# CTR-Controller-Rev-A-LED-5.net
KiCad netlist of a schematic drawn in Altium Designer
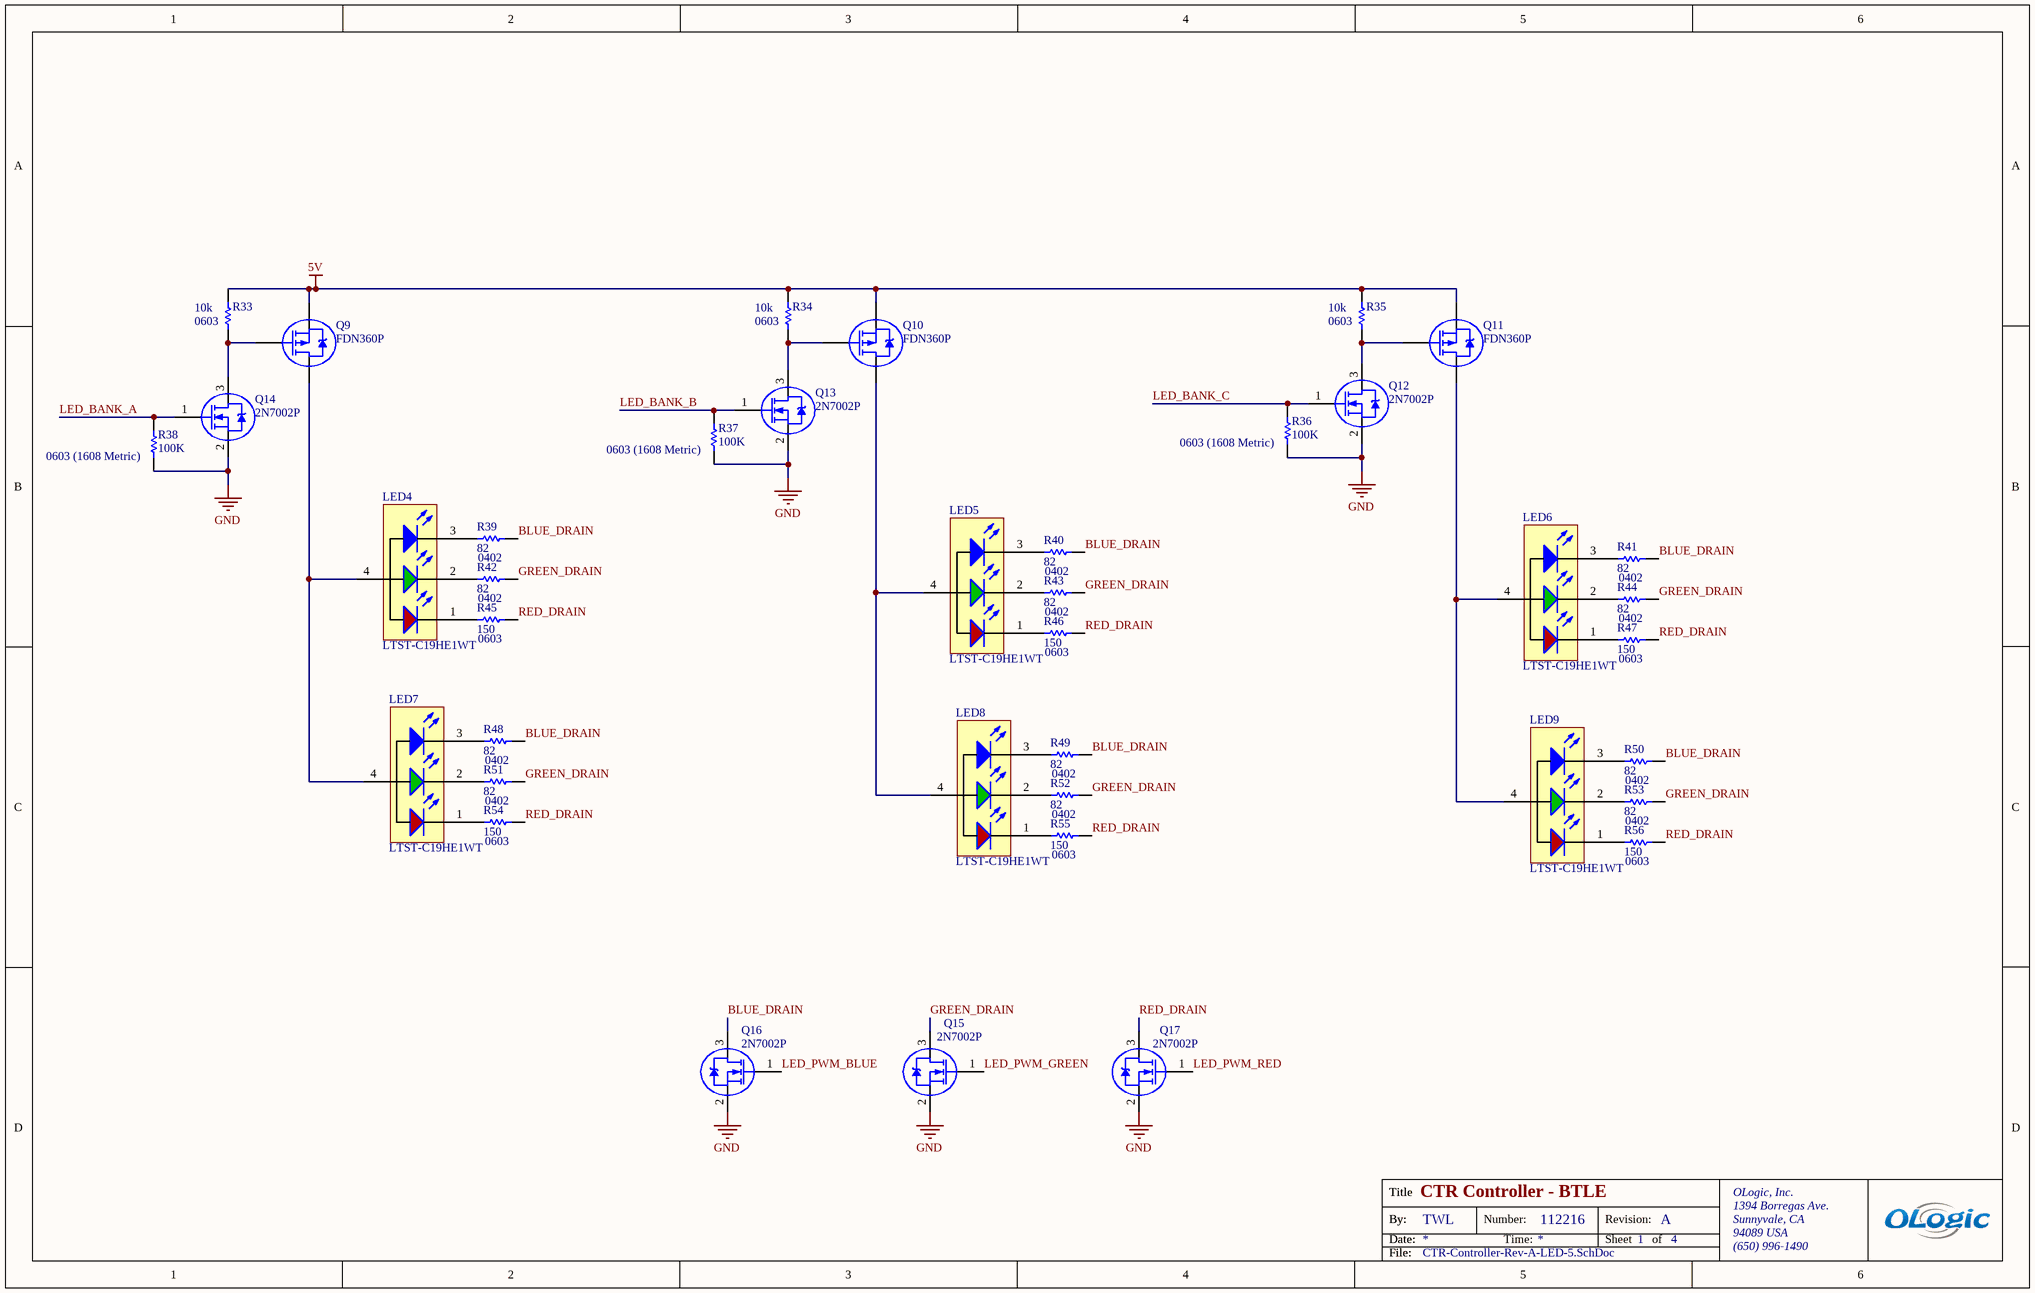
[diagram p0: CTR-Controller-Rev-A-LED-5.SchDoc]

(export (version "E")
  (design (tool "Eeschema 10.0.6"))
  (components
    (comp (ref "LED4")
      (value "Red, Green, Blue (RGB)")
      (footprint "LTST-C19HE1WT")
      (description "LED RGB 624/525/470NM DIFF SMD")
      (fields
        (field (name "MANUFACTURER") "Lite-On Inc.")
        (field (name "MANUFACTURER PART NUMBER") "LTST-C19HE1WT")
      )
      (libsource (lib "OLogic-Diode-Opto-LED") (part "LTST-C19HE1WT"))
    )
    (comp (ref "LED5")
      (value "Red, Green, Blue (RGB)")
      (footprint "LTST-C19HE1WT")
      (description "LED RGB 624/525/470NM DIFF SMD")
      (fields
        (field (name "MANUFACTURER") "Lite-On Inc.")
        (field (name "MANUFACTURER PART NUMBER") "LTST-C19HE1WT")
      )
      (libsource (lib "OLogic-Diode-Opto-LED") (part "LTST-C19HE1WT"))
    )
    (comp (ref "LED6")
      (value "Red, Green, Blue (RGB)")
      (footprint "LTST-C19HE1WT")
      (description "LED RGB 624/525/470NM DIFF SMD")
      (fields
        (field (name "MANUFACTURER") "Lite-On Inc.")
        (field (name "MANUFACTURER PART NUMBER") "LTST-C19HE1WT")
      )
      (libsource (lib "OLogic-Diode-Opto-LED") (part "LTST-C19HE1WT"))
    )
    (comp (ref "LED7")
      (value "Red, Green, Blue (RGB)")
      (footprint "LTST-C19HE1WT")
      (description "LED RGB 624/525/470NM DIFF SMD")
      (fields
        (field (name "MANUFACTURER") "Lite-On Inc.")
        (field (name "MANUFACTURER PART NUMBER") "LTST-C19HE1WT")
      )
      (libsource (lib "OLogic-Diode-Opto-LED") (part "LTST-C19HE1WT"))
    )
    (comp (ref "LED8")
      (value "Red, Green, Blue (RGB)")
      (footprint "LTST-C19HE1WT")
      (description "LED RGB 624/525/470NM DIFF SMD")
      (fields
        (field (name "MANUFACTURER") "Lite-On Inc.")
        (field (name "MANUFACTURER PART NUMBER") "LTST-C19HE1WT")
      )
      (libsource (lib "OLogic-Diode-Opto-LED") (part "LTST-C19HE1WT"))
    )
    (comp (ref "LED9")
      (value "Red, Green, Blue (RGB)")
      (footprint "LTST-C19HE1WT")
      (description "LED RGB 624/525/470NM DIFF SMD")
      (fields
        (field (name "MANUFACTURER") "Lite-On Inc.")
        (field (name "MANUFACTURER PART NUMBER") "LTST-C19HE1WT")
      )
      (libsource (lib "OLogic-Diode-Opto-LED") (part "LTST-C19HE1WT"))
    )
    (comp (ref "Q9")
      (value "FDN360P")
      (footprint "SOT23")
      (description "Single P-Channel MOSFET")
      (fields (field (name "MANUFACTURER") "Fairchild Semi"))
      (libsource (lib "OLogic-Trans-Drivers") (part "FDN360P"))
    )
    (comp (ref "Q10")
      (value "FDN360P")
      (footprint "SOT23")
      (description "Single P-Channel MOSFET")
      (fields (field (name "MANUFACTURER") "Fairchild Semi"))
      (libsource (lib "OLogic-Trans-Drivers") (part "FDN360P"))
    )
    (comp (ref "Q11")
      (value "FDN360P")
      (footprint "SOT23")
      (description "Single P-Channel MOSFET")
      (fields (field (name "MANUFACTURER") "Fairchild Semi"))
      (libsource (lib "OLogic-Trans-Drivers") (part "FDN360P"))
    )
    (comp (ref "Q12")
      (value "2N7002P")
      (footprint "SOT23")
      (description "MOSFET N-CH 60V 0.36A SOT-23")
      (fields
        (field (name "MANUFACTURER") "NXP Semiconductors")
        (field (name "MANUFACTURER PART NUMBER") "2N7002P,235")
      )
      (libsource (lib "") (part "2N7002P_1"))
    )
    (comp (ref "Q13")
      (value "2N7002P")
      (footprint "SOT23")
      (description "MOSFET N-CH 60V 0.36A SOT-23")
      (fields
        (field (name "MANUFACTURER") "NXP Semiconductors")
        (field (name "MANUFACTURER PART NUMBER") "2N7002P,235")
      )
      (libsource (lib "") (part "2N7002P_1"))
    )
    (comp (ref "Q14")
      (value "2N7002P")
      (footprint "SOT23")
      (description "MOSFET N-CH 60V 0.36A SOT-23")
      (fields
        (field (name "MANUFACTURER") "NXP Semiconductors")
        (field (name "MANUFACTURER PART NUMBER") "2N7002P,235")
      )
      (libsource (lib "") (part "2N7002P_1"))
    )
    (comp (ref "Q15")
      (value "2N7002P")
      (footprint "SOT23")
      (description "MOSFET N-CH 60V 0.36A SOT-23")
      (fields
        (field (name "MANUFACTURER") "NXP Semiconductors")
        (field (name "MANUFACTURER PART NUMBER") "2N7002P,235")
      )
      (libsource (lib "OLogic-Trans-Drivers") (part "2N7002P"))
    )
    (comp (ref "Q16")
      (value "2N7002P")
      (footprint "SOT23")
      (description "MOSFET N-CH 60V 0.36A SOT-23")
      (fields
        (field (name "MANUFACTURER") "NXP Semiconductors")
        (field (name "MANUFACTURER PART NUMBER") "2N7002P,235")
      )
      (libsource (lib "OLogic-Trans-Drivers") (part "2N7002P"))
    )
    (comp (ref "Q17")
      (value "2N7002P")
      (footprint "SOT23")
      (description "MOSFET N-CH 60V 0.36A SOT-23")
      (fields
        (field (name "MANUFACTURER") "NXP Semiconductors")
        (field (name "MANUFACTURER PART NUMBER") "2N7002P,235")
      )
      (libsource (lib "OLogic-Trans-Drivers") (part "2N7002P"))
    )
    (comp (ref "R33")
      (value "10K 1%")
      (footprint "RESC0603(1608)_N")
      (description "10K 0603")
      (fields
        (field (name "MANUFACTURER") "Panasonic Electronic Components")
        (field (name "MANUFACTURER PART NUMBER") "ERJ-3EKF1002V")
        (field (name "RESISTANCE (OHMS)") "10k")
        (field (name "SUPPLIER DEVICE PACKAGE") "0603")
      )
      (libsource (lib "OLogic-Passive") (part "RES 10K OHM 1/10W 1% 0603 SMD"))
    )
    (comp (ref "R34")
      (value "10K 1%")
      (footprint "RESC0603(1608)_N")
      (description "10K 0603")
      (fields
        (field (name "MANUFACTURER") "Panasonic Electronic Components")
        (field (name "MANUFACTURER PART NUMBER") "ERJ-3EKF1002V")
        (field (name "RESISTANCE (OHMS)") "10k")
        (field (name "SUPPLIER DEVICE PACKAGE") "0603")
      )
      (libsource (lib "OLogic-Passive") (part "RES 10K OHM 1/10W 1% 0603 SMD"))
    )
    (comp (ref "R35")
      (value "10K 1%")
      (footprint "RESC0603(1608)_N")
      (description "10K 0603")
      (fields
        (field (name "MANUFACTURER") "Panasonic Electronic Components")
        (field (name "MANUFACTURER PART NUMBER") "ERJ-3EKF1002V")
        (field (name "RESISTANCE (OHMS)") "10k")
        (field (name "SUPPLIER DEVICE PACKAGE") "0603")
      )
      (libsource (lib "OLogic-Passive") (part "RES 10K OHM 1/10W 1% 0603 SMD"))
    )
    (comp (ref "R36")
      (value "100K")
      (footprint "RESC0603(1608)_N")
      (description "100K 0603")
      (fields
        (field (name "MANUFACTURER") "Rohm Semiconductor")
        (field (name "MANUFACTURER PART NUMBER") "ESR03EZPJ104")
        (field (name "PACKAGE / CASE") "0603 (1608 Metric)")
      )
      (libsource (lib "OLogic-Passive") (part "RES 100K OHM 5% 1/4W 0603"))
    )
    (comp (ref "R37")
      (value "100K")
      (footprint "RESC0603(1608)_N")
      (description "100K 0603")
      (fields
        (field (name "MANUFACTURER") "Rohm Semiconductor")
        (field (name "MANUFACTURER PART NUMBER") "ESR03EZPJ104")
        (field (name "PACKAGE / CASE") "0603 (1608 Metric)")
      )
      (libsource (lib "OLogic-Passive") (part "RES 100K OHM 5% 1/4W 0603"))
    )
    (comp (ref "R38")
      (value "100K")
      (footprint "RESC0603(1608)_N")
      (description "100K 0603")
      (fields
        (field (name "MANUFACTURER") "Rohm Semiconductor")
        (field (name "MANUFACTURER PART NUMBER") "ESR03EZPJ104")
        (field (name "PACKAGE / CASE") "0603 (1608 Metric)")
      )
      (libsource (lib "OLogic-Passive") (part "RES 100K OHM 5% 1/4W 0603"))
    )
    (comp (ref "R39")
      (value "?")
      (footprint "RESC0402(1005)_N")
      (description "82 0402")
      (fields
        (field (name "MANUFACTURER") "Panasonic Electronic Components")
        (field (name "MANUFACTURER PART NUMBER") "ERJ-2RKF82R0X")
        (field (name "SUPPLIER DEVICE PACKAGE") "0402")
        (field (name "RESISTANCE (OHMS)") "82")
        (field (name "CREATOR") "osman")
      )
      (libsource (lib "OLogic-Passive") (part "RES 82 OHM 1% 1/10W 0402"))
    )
    (comp (ref "R40")
      (value "?")
      (footprint "RESC0402(1005)_N")
      (description "82 0402")
      (fields
        (field (name "MANUFACTURER") "Panasonic Electronic Components")
        (field (name "MANUFACTURER PART NUMBER") "ERJ-2RKF82R0X")
        (field (name "SUPPLIER DEVICE PACKAGE") "0402")
        (field (name "RESISTANCE (OHMS)") "82")
        (field (name "CREATOR") "osman")
      )
      (libsource (lib "OLogic-Passive") (part "RES 82 OHM 1% 1/10W 0402"))
    )
    (comp (ref "R41")
      (value "?")
      (footprint "RESC0402(1005)_N")
      (description "82 0402")
      (fields
        (field (name "MANUFACTURER") "Panasonic Electronic Components")
        (field (name "MANUFACTURER PART NUMBER") "ERJ-2RKF82R0X")
        (field (name "SUPPLIER DEVICE PACKAGE") "0402")
        (field (name "RESISTANCE (OHMS)") "82")
        (field (name "CREATOR") "osman")
      )
      (libsource (lib "OLogic-Passive") (part "RES 82 OHM 1% 1/10W 0402"))
    )
    (comp (ref "R42")
      (value "?")
      (footprint "RESC0402(1005)_N")
      (description "82 0402")
      (fields
        (field (name "MANUFACTURER") "Panasonic Electronic Components")
        (field (name "MANUFACTURER PART NUMBER") "ERJ-2RKF82R0X")
        (field (name "SUPPLIER DEVICE PACKAGE") "0402")
        (field (name "RESISTANCE (OHMS)") "82")
        (field (name "CREATOR") "osman")
      )
      (libsource (lib "OLogic-Passive") (part "RES 82 OHM 1% 1/10W 0402"))
    )
    (comp (ref "R43")
      (value "?")
      (footprint "RESC0402(1005)_N")
      (description "82 0402")
      (fields
        (field (name "MANUFACTURER") "Panasonic Electronic Components")
        (field (name "MANUFACTURER PART NUMBER") "ERJ-2RKF82R0X")
        (field (name "SUPPLIER DEVICE PACKAGE") "0402")
        (field (name "RESISTANCE (OHMS)") "82")
        (field (name "CREATOR") "osman")
      )
      (libsource (lib "OLogic-Passive") (part "RES 82 OHM 1% 1/10W 0402"))
    )
    (comp (ref "R44")
      (value "?")
      (footprint "RESC0402(1005)_N")
      (description "82 0402")
      (fields
        (field (name "MANUFACTURER") "Panasonic Electronic Components")
        (field (name "MANUFACTURER PART NUMBER") "ERJ-2RKF82R0X")
        (field (name "SUPPLIER DEVICE PACKAGE") "0402")
        (field (name "RESISTANCE (OHMS)") "82")
        (field (name "CREATOR") "osman")
      )
      (libsource (lib "OLogic-Passive") (part "RES 82 OHM 1% 1/10W 0402"))
    )
    (comp (ref "R45")
      (value "150")
      (footprint "RESC0603(1608)_N")
      (description "150 0603")
      (fields
        (field (name "MANUFACTURER") "Yageo")
        (field (name "MANUFACTURER PART NUMBER") "RC0603FR-07150RL")
        (field (name "SUPPLIER DEVICE PACKAGE") "0603")
      )
      (libsource (lib "OLogic-Passive") (part "RES 150 OHM 1/10W 1% 0603 SMD"))
    )
    (comp (ref "R46")
      (value "150")
      (footprint "RESC0603(1608)_N")
      (description "150 0603")
      (fields
        (field (name "MANUFACTURER") "Yageo")
        (field (name "MANUFACTURER PART NUMBER") "RC0603FR-07150RL")
        (field (name "SUPPLIER DEVICE PACKAGE") "0603")
      )
      (libsource (lib "OLogic-Passive") (part "RES 150 OHM 1/10W 1% 0603 SMD"))
    )
    (comp (ref "R47")
      (value "150")
      (footprint "RESC0603(1608)_N")
      (description "150 0603")
      (fields
        (field (name "MANUFACTURER") "Yageo")
        (field (name "MANUFACTURER PART NUMBER") "RC0603FR-07150RL")
        (field (name "SUPPLIER DEVICE PACKAGE") "0603")
      )
      (libsource (lib "OLogic-Passive") (part "RES 150 OHM 1/10W 1% 0603 SMD"))
    )
    (comp (ref "R48")
      (value "?")
      (footprint "RESC0402(1005)_N")
      (description "82 0402")
      (fields
        (field (name "MANUFACTURER") "Panasonic Electronic Components")
        (field (name "MANUFACTURER PART NUMBER") "ERJ-2RKF82R0X")
        (field (name "SUPPLIER DEVICE PACKAGE") "0402")
        (field (name "RESISTANCE (OHMS)") "82")
        (field (name "CREATOR") "osman")
      )
      (libsource (lib "OLogic-Passive") (part "RES 82 OHM 1% 1/10W 0402"))
    )
    (comp (ref "R49")
      (value "?")
      (footprint "RESC0402(1005)_N")
      (description "82 0402")
      (fields
        (field (name "MANUFACTURER") "Panasonic Electronic Components")
        (field (name "MANUFACTURER PART NUMBER") "ERJ-2RKF82R0X")
        (field (name "SUPPLIER DEVICE PACKAGE") "0402")
        (field (name "RESISTANCE (OHMS)") "82")
        (field (name "CREATOR") "osman")
      )
      (libsource (lib "OLogic-Passive") (part "RES 82 OHM 1% 1/10W 0402"))
    )
    (comp (ref "R50")
      (value "?")
      (footprint "RESC0402(1005)_N")
      (description "82 0402")
      (fields
        (field (name "MANUFACTURER") "Panasonic Electronic Components")
        (field (name "MANUFACTURER PART NUMBER") "ERJ-2RKF82R0X")
        (field (name "SUPPLIER DEVICE PACKAGE") "0402")
        (field (name "RESISTANCE (OHMS)") "82")
        (field (name "CREATOR") "osman")
      )
      (libsource (lib "OLogic-Passive") (part "RES 82 OHM 1% 1/10W 0402"))
    )
    (comp (ref "R51")
      (value "?")
      (footprint "RESC0402(1005)_N")
      (description "82 0402")
      (fields
        (field (name "MANUFACTURER") "Panasonic Electronic Components")
        (field (name "MANUFACTURER PART NUMBER") "ERJ-2RKF82R0X")
        (field (name "SUPPLIER DEVICE PACKAGE") "0402")
        (field (name "RESISTANCE (OHMS)") "82")
        (field (name "CREATOR") "osman")
      )
      (libsource (lib "OLogic-Passive") (part "RES 82 OHM 1% 1/10W 0402"))
    )
    (comp (ref "R52")
      (value "?")
      (footprint "RESC0402(1005)_N")
      (description "82 0402")
      (fields
        (field (name "MANUFACTURER") "Panasonic Electronic Components")
        (field (name "MANUFACTURER PART NUMBER") "ERJ-2RKF82R0X")
        (field (name "SUPPLIER DEVICE PACKAGE") "0402")
        (field (name "RESISTANCE (OHMS)") "82")
        (field (name "CREATOR") "osman")
      )
      (libsource (lib "OLogic-Passive") (part "RES 82 OHM 1% 1/10W 0402"))
    )
    (comp (ref "R53")
      (value "?")
      (footprint "RESC0402(1005)_N")
      (description "82 0402")
      (fields
        (field (name "MANUFACTURER") "Panasonic Electronic Components")
        (field (name "MANUFACTURER PART NUMBER") "ERJ-2RKF82R0X")
        (field (name "SUPPLIER DEVICE PACKAGE") "0402")
        (field (name "RESISTANCE (OHMS)") "82")
        (field (name "CREATOR") "osman")
      )
      (libsource (lib "OLogic-Passive") (part "RES 82 OHM 1% 1/10W 0402"))
    )
    (comp (ref "R54")
      (value "150")
      (footprint "RESC0603(1608)_N")
      (description "150 0603")
      (fields
        (field (name "MANUFACTURER") "Yageo")
        (field (name "MANUFACTURER PART NUMBER") "RC0603FR-07150RL")
        (field (name "SUPPLIER DEVICE PACKAGE") "0603")
      )
      (libsource (lib "OLogic-Passive") (part "RES 150 OHM 1/10W 1% 0603 SMD"))
    )
    (comp (ref "R55")
      (value "150")
      (footprint "RESC0603(1608)_N")
      (description "150 0603")
      (fields
        (field (name "MANUFACTURER") "Yageo")
        (field (name "MANUFACTURER PART NUMBER") "RC0603FR-07150RL")
        (field (name "SUPPLIER DEVICE PACKAGE") "0603")
      )
      (libsource (lib "OLogic-Passive") (part "RES 150 OHM 1/10W 1% 0603 SMD"))
    )
    (comp (ref "R56")
      (value "150")
      (footprint "RESC0603(1608)_N")
      (description "150 0603")
      (fields
        (field (name "MANUFACTURER") "Yageo")
        (field (name "MANUFACTURER PART NUMBER") "RC0603FR-07150RL")
        (field (name "SUPPLIER DEVICE PACKAGE") "0603")
      )
      (libsource (lib "OLogic-Passive") (part "RES 150 OHM 1/10W 1% 0603 SMD"))
    )
  )
  (nets
    (net (code "1") (name "/BLUE_DRAIN") (class "Default")
      (node (ref "Q16") (pin "3") (pinfunction "D_3") (pintype "power_in"))
      (node (ref "R39") (pin "1") (pinfunction "1_1") (pintype "passive"))
      (node (ref "R40") (pin "1") (pinfunction "1_1") (pintype "passive"))
      (node (ref "R41") (pin "1") (pinfunction "1_1") (pintype "passive"))
      (node (ref "R48") (pin "1") (pinfunction "1_1") (pintype "passive"))
      (node (ref "R49") (pin "1") (pinfunction "1_1") (pintype "passive"))
      (node (ref "R50") (pin "1") (pinfunction "1_1") (pintype "passive"))
    )
    (net (code "2") (name "/GREEN_DRAIN") (class "Default")
      (node (ref "Q15") (pin "3") (pinfunction "D_3") (pintype "power_in"))
      (node (ref "R42") (pin "1") (pinfunction "1_1") (pintype "passive"))
      (node (ref "R43") (pin "1") (pinfunction "1_1") (pintype "passive"))
      (node (ref "R44") (pin "1") (pinfunction "1_1") (pintype "passive"))
      (node (ref "R51") (pin "1") (pinfunction "1_1") (pintype "passive"))
      (node (ref "R52") (pin "1") (pinfunction "1_1") (pintype "passive"))
      (node (ref "R53") (pin "1") (pinfunction "1_1") (pintype "passive"))
    )
    (net (code "3") (name "/LED_BANK_A") (class "Default")
      (node (ref "Q14") (pin "1") (pinfunction "G_1") (pintype "passive"))
      (node (ref "R38") (pin "2") (pinfunction "2_2") (pintype "passive"))
    )
    (net (code "4") (name "/LED_BANK_B") (class "Default")
      (node (ref "Q13") (pin "1") (pinfunction "G_1") (pintype "passive"))
      (node (ref "R37") (pin "2") (pinfunction "2_2") (pintype "passive"))
    )
    (net (code "5") (name "/LED_BANK_C") (class "Default")
      (node (ref "Q12") (pin "1") (pinfunction "G_1") (pintype "passive"))
      (node (ref "R36") (pin "2") (pinfunction "2_2") (pintype "passive"))
    )
    (net (code "6") (name "/LED_PWM_BLUE") (class "Default")
      (node (ref "Q16") (pin "1") (pinfunction "G_1") (pintype "passive"))
    )
    (net (code "7") (name "/LED_PWM_GREEN") (class "Default")
      (node (ref "Q15") (pin "1") (pinfunction "G_1") (pintype "passive"))
    )
    (net (code "8") (name "/LED_PWM_RED") (class "Default")
      (node (ref "Q17") (pin "1") (pinfunction "G_1") (pintype "passive"))
    )
    (net (code "9") (name "/RED_DRAIN") (class "Default")
      (node (ref "Q17") (pin "3") (pinfunction "D_3") (pintype "power_in"))
      (node (ref "R45") (pin "1") (pinfunction "1_1") (pintype "passive"))
      (node (ref "R46") (pin "1") (pinfunction "1_1") (pintype "passive"))
      (node (ref "R47") (pin "1") (pinfunction "1_1") (pintype "passive"))
      (node (ref "R54") (pin "1") (pinfunction "1_1") (pintype "passive"))
      (node (ref "R55") (pin "1") (pinfunction "1_1") (pintype "passive"))
      (node (ref "R56") (pin "1") (pinfunction "1_1") (pintype "passive"))
    )
    (net (code "10") (name "5V") (class "Default")
      (node (ref "Q10") (pin "2") (pinfunction "S_2") (pintype "passive"))
      (node (ref "Q11") (pin "2") (pinfunction "S_2") (pintype "passive"))
      (node (ref "Q9") (pin "2") (pinfunction "S_2") (pintype "passive"))
      (node (ref "R33") (pin "2") (pinfunction "2_2") (pintype "passive"))
      (node (ref "R34") (pin "2") (pinfunction "2_2") (pintype "passive"))
      (node (ref "R35") (pin "2") (pinfunction "2_2") (pintype "passive"))
    )
    (net (code "11") (name "GND") (class "Default")
      (node (ref "Q12") (pin "2") (pinfunction "S_2") (pintype "passive"))
      (node (ref "Q13") (pin "2") (pinfunction "S_2") (pintype "passive"))
      (node (ref "Q14") (pin "2") (pinfunction "S_2") (pintype "passive"))
      (node (ref "Q15") (pin "2") (pinfunction "S_2") (pintype "passive"))
      (node (ref "Q16") (pin "2") (pinfunction "S_2") (pintype "passive"))
      (node (ref "Q17") (pin "2") (pinfunction "S_2") (pintype "passive"))
      (node (ref "R36") (pin "1") (pinfunction "1_1") (pintype "passive"))
      (node (ref "R37") (pin "1") (pinfunction "1_1") (pintype "passive"))
      (node (ref "R38") (pin "1") (pinfunction "1_1") (pintype "passive"))
    )
    (net (code "12") (name "Net-(LED4-Anode)") (class "Default")
      (node (ref "LED4") (pin "4") (pinfunction "Anode_4") (pintype "passive"))
      (node (ref "LED7") (pin "4") (pinfunction "Anode_4") (pintype "passive"))
      (node (ref "Q9") (pin "3") (pinfunction "D_3") (pintype "passive"))
    )
    (net (code "13") (name "Net-(LED4-B)") (class "Default")
      (node (ref "LED4") (pin "3") (pinfunction "B_3") (pintype "passive"))
      (node (ref "R39") (pin "2") (pinfunction "2_2") (pintype "passive"))
    )
    (net (code "14") (name "Net-(LED4-G)") (class "Default")
      (node (ref "LED4") (pin "2") (pinfunction "G_2") (pintype "passive"))
      (node (ref "R42") (pin "2") (pinfunction "2_2") (pintype "passive"))
    )
    (net (code "15") (name "Net-(LED4-R)") (class "Default")
      (node (ref "LED4") (pin "1") (pinfunction "R_1") (pintype "passive"))
      (node (ref "R45") (pin "2") (pinfunction "2_2") (pintype "passive"))
    )
    (net (code "16") (name "Net-(LED5-Anode)") (class "Default")
      (node (ref "LED5") (pin "4") (pinfunction "Anode_4") (pintype "passive"))
      (node (ref "LED8") (pin "4") (pinfunction "Anode_4") (pintype "passive"))
      (node (ref "Q10") (pin "3") (pinfunction "D_3") (pintype "passive"))
    )
    (net (code "17") (name "Net-(LED5-B)") (class "Default")
      (node (ref "LED5") (pin "3") (pinfunction "B_3") (pintype "passive"))
      (node (ref "R40") (pin "2") (pinfunction "2_2") (pintype "passive"))
    )
    (net (code "18") (name "Net-(LED5-G)") (class "Default")
      (node (ref "LED5") (pin "2") (pinfunction "G_2") (pintype "passive"))
      (node (ref "R43") (pin "2") (pinfunction "2_2") (pintype "passive"))
    )
    (net (code "19") (name "Net-(LED5-R)") (class "Default")
      (node (ref "LED5") (pin "1") (pinfunction "R_1") (pintype "passive"))
      (node (ref "R46") (pin "2") (pinfunction "2_2") (pintype "passive"))
    )
    (net (code "20") (name "Net-(LED6-Anode)") (class "Default")
      (node (ref "LED6") (pin "4") (pinfunction "Anode_4") (pintype "passive"))
      (node (ref "LED9") (pin "4") (pinfunction "Anode_4") (pintype "passive"))
      (node (ref "Q11") (pin "3") (pinfunction "D_3") (pintype "passive"))
    )
    (net (code "21") (name "Net-(LED6-B)") (class "Default")
      (node (ref "LED6") (pin "3") (pinfunction "B_3") (pintype "passive"))
      (node (ref "R41") (pin "2") (pinfunction "2_2") (pintype "passive"))
    )
    (net (code "22") (name "Net-(LED6-G)") (class "Default")
      (node (ref "LED6") (pin "2") (pinfunction "G_2") (pintype "passive"))
      (node (ref "R44") (pin "2") (pinfunction "2_2") (pintype "passive"))
    )
    (net (code "23") (name "Net-(LED6-R)") (class "Default")
      (node (ref "LED6") (pin "1") (pinfunction "R_1") (pintype "passive"))
      (node (ref "R47") (pin "2") (pinfunction "2_2") (pintype "passive"))
    )
    (net (code "24") (name "Net-(LED7-B)") (class "Default")
      (node (ref "LED7") (pin "3") (pinfunction "B_3") (pintype "passive"))
      (node (ref "R48") (pin "2") (pinfunction "2_2") (pintype "passive"))
    )
    (net (code "25") (name "Net-(LED7-G)") (class "Default")
      (node (ref "LED7") (pin "2") (pinfunction "G_2") (pintype "passive"))
      (node (ref "R51") (pin "2") (pinfunction "2_2") (pintype "passive"))
    )
    (net (code "26") (name "Net-(LED7-R)") (class "Default")
      (node (ref "LED7") (pin "1") (pinfunction "R_1") (pintype "passive"))
      (node (ref "R54") (pin "2") (pinfunction "2_2") (pintype "passive"))
    )
    (net (code "27") (name "Net-(LED8-B)") (class "Default")
      (node (ref "LED8") (pin "3") (pinfunction "B_3") (pintype "passive"))
      (node (ref "R49") (pin "2") (pinfunction "2_2") (pintype "passive"))
    )
    (net (code "28") (name "Net-(LED8-G)") (class "Default")
      (node (ref "LED8") (pin "2") (pinfunction "G_2") (pintype "passive"))
      (node (ref "R52") (pin "2") (pinfunction "2_2") (pintype "passive"))
    )
    (net (code "29") (name "Net-(LED8-R)") (class "Default")
      (node (ref "LED8") (pin "1") (pinfunction "R_1") (pintype "passive"))
      (node (ref "R55") (pin "2") (pinfunction "2_2") (pintype "passive"))
    )
    (net (code "30") (name "Net-(LED9-B)") (class "Default")
      (node (ref "LED9") (pin "3") (pinfunction "B_3") (pintype "passive"))
      (node (ref "R50") (pin "2") (pinfunction "2_2") (pintype "passive"))
    )
    (net (code "31") (name "Net-(LED9-G)") (class "Default")
      (node (ref "LED9") (pin "2") (pinfunction "G_2") (pintype "passive"))
      (node (ref "R53") (pin "2") (pinfunction "2_2") (pintype "passive"))
    )
    (net (code "32") (name "Net-(LED9-R)") (class "Default")
      (node (ref "LED9") (pin "1") (pinfunction "R_1") (pintype "passive"))
      (node (ref "R56") (pin "2") (pinfunction "2_2") (pintype "passive"))
    )
    (net (code "33") (name "Net-(Q10-G)") (class "Default")
      (node (ref "Q10") (pin "1") (pinfunction "G_1") (pintype "passive"))
      (node (ref "Q13") (pin "3") (pinfunction "D_3") (pintype "power_in"))
      (node (ref "R34") (pin "1") (pinfunction "1_1") (pintype "passive"))
    )
    (net (code "34") (name "Net-(Q11-G)") (class "Default")
      (node (ref "Q11") (pin "1") (pinfunction "G_1") (pintype "passive"))
      (node (ref "Q12") (pin "3") (pinfunction "D_3") (pintype "power_in"))
      (node (ref "R35") (pin "1") (pinfunction "1_1") (pintype "passive"))
    )
    (net (code "35") (name "Net-(Q14-D)") (class "Default")
      (node (ref "Q14") (pin "3") (pinfunction "D_3") (pintype "power_in"))
      (node (ref "Q9") (pin "1") (pinfunction "G_1") (pintype "passive"))
      (node (ref "R33") (pin "1") (pinfunction "1_1") (pintype "passive"))
    )
  )
)
